# Reference_distribution.net
KiCad netlist of a schematic drawn in Altium Designer
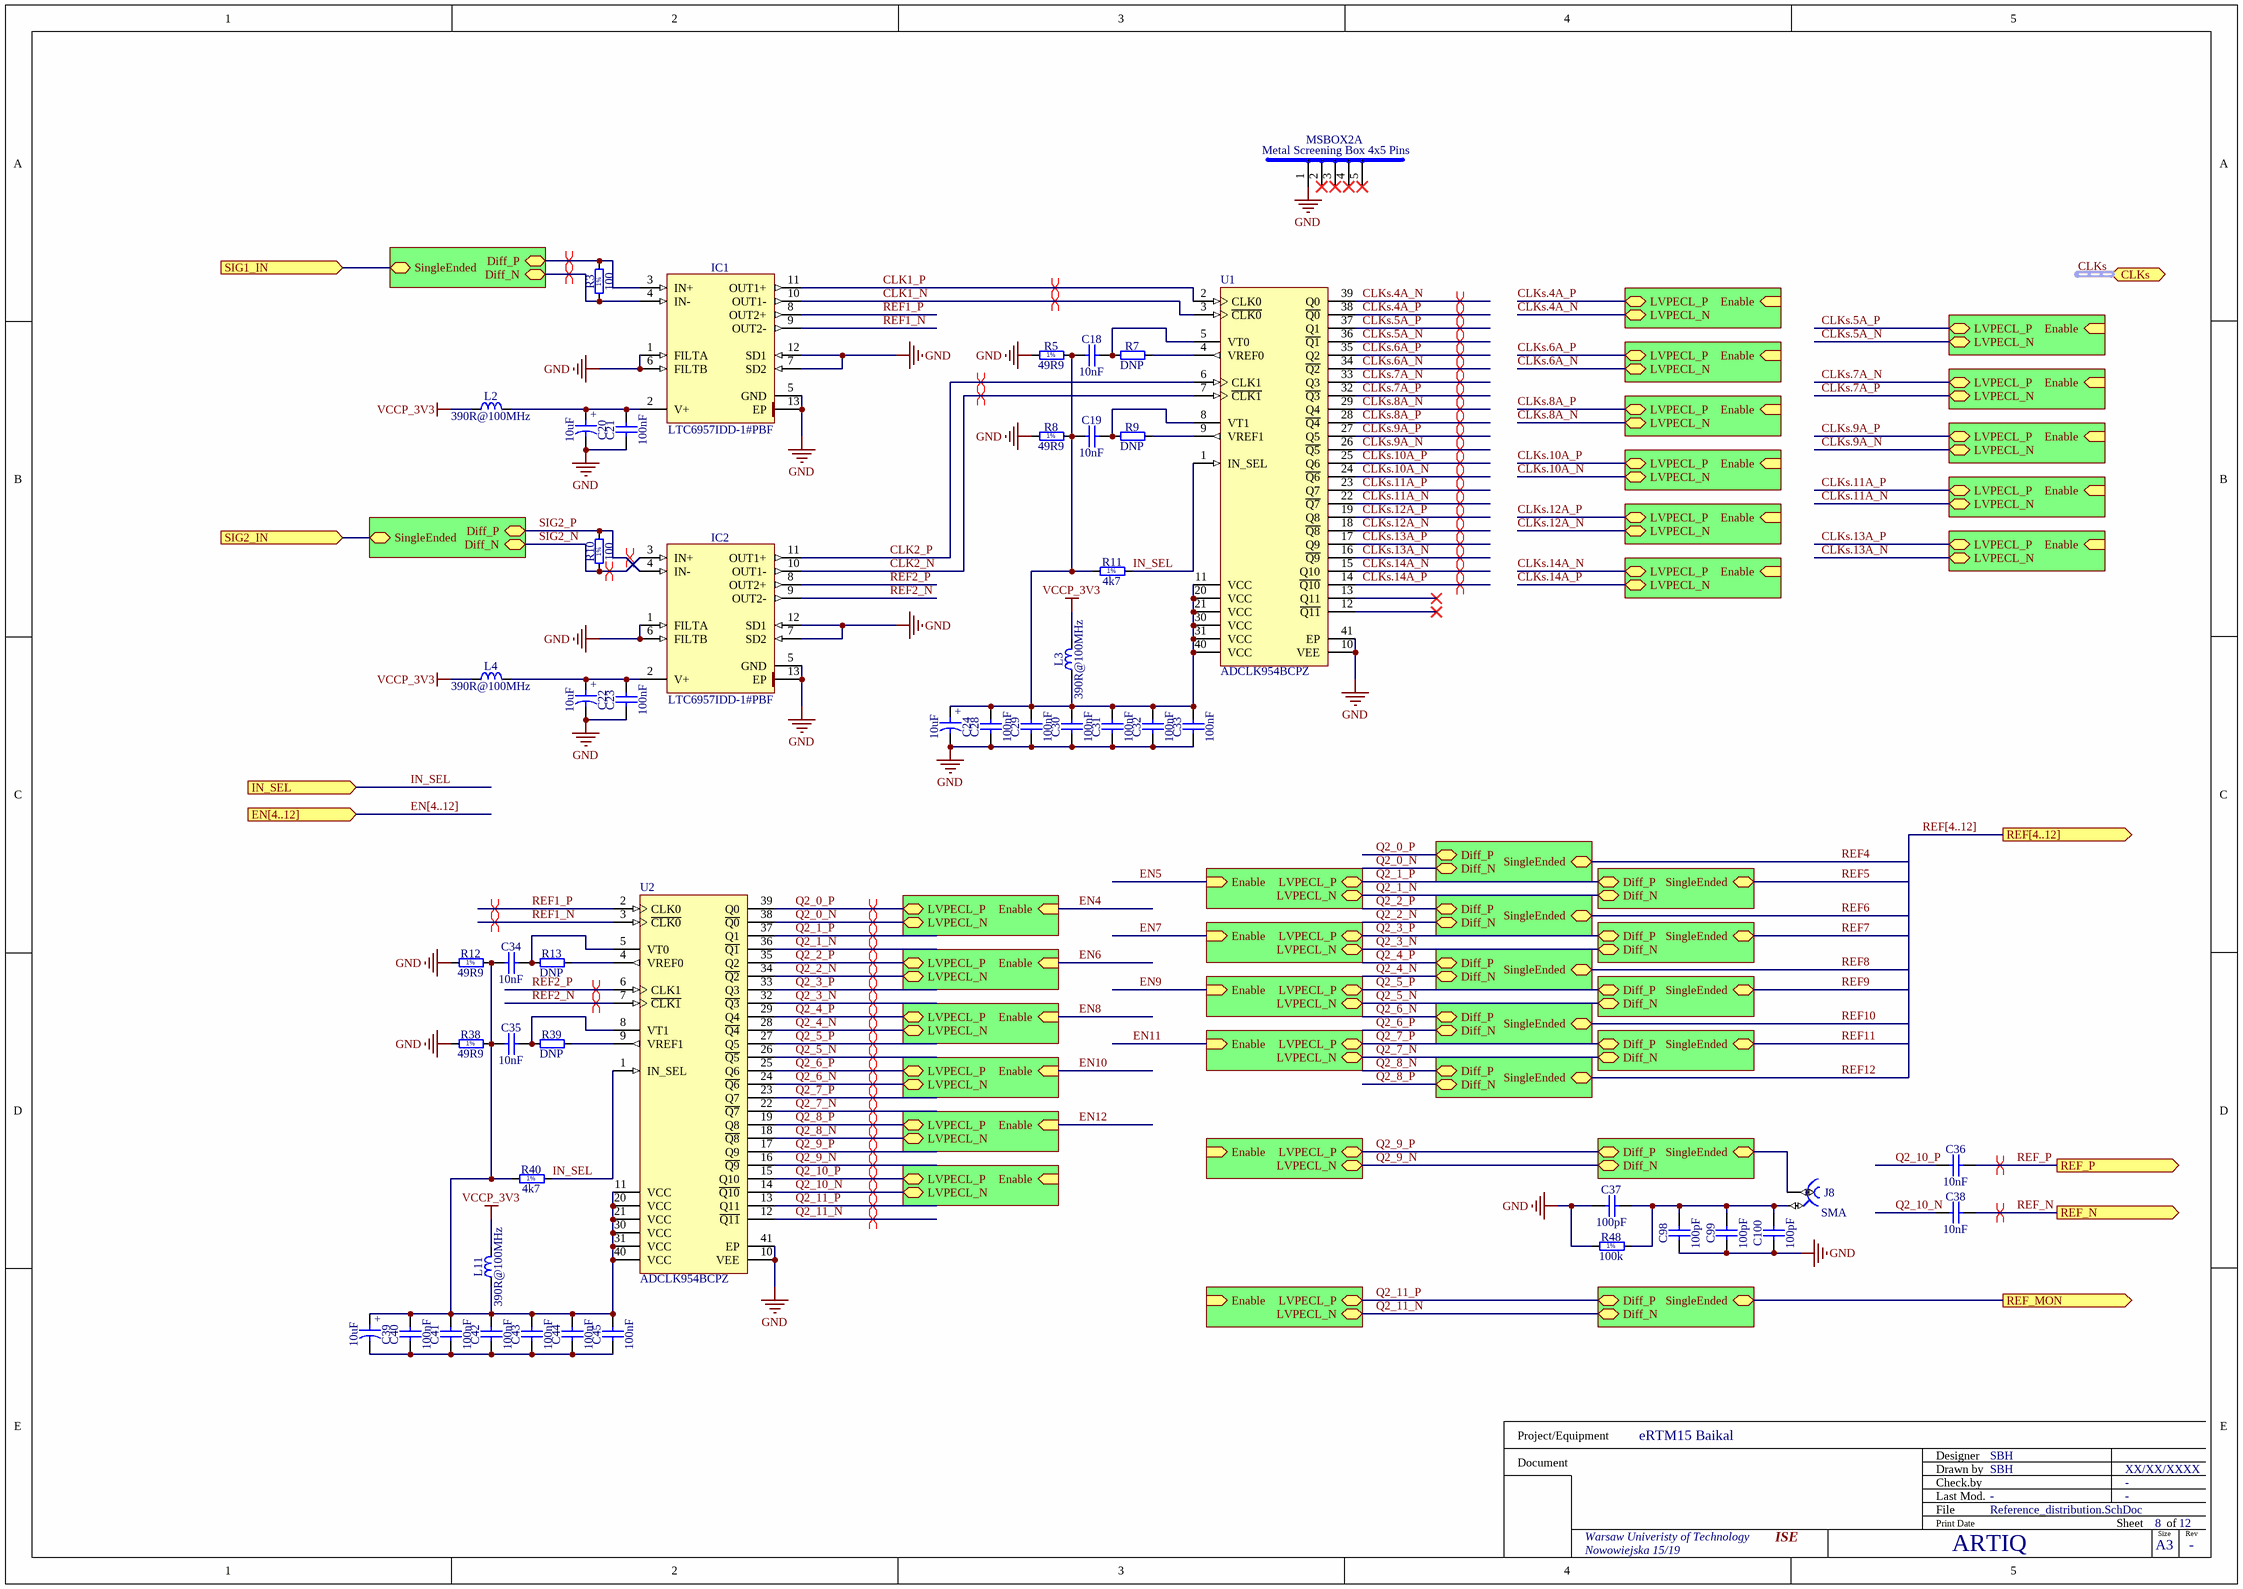
[diagram p0: Reference_distribution.SchDoc]

(export (version "E")
  (design (tool "Eeschema 10.0.6"))
  (components
    (comp (ref "C18")
      (value "10nF")
      (footprint "CAPC1005X55N")
      (description "Non-polarised capacitor")
      (fields
        (field (name "PART NUMBER") "CC0402_10NF_16V_10%_X7R")
        (field (name "VOLTAGE") "16V")
        (field (name "AUTHOR") "CERN DEM JLC")
      )
      (libsource (lib "Capacitors") (part "Capacitor - non polarized"))
    )
    (comp (ref "C19")
      (value "10nF")
      (footprint "CAPC1005X55N")
      (description "Non-polarised capacitor")
      (fields
        (field (name "PART NUMBER") "CC0402_10NF_16V_10%_X7R")
        (field (name "VOLTAGE") "16V")
        (field (name "AUTHOR") "CERN DEM JLC")
      )
      (libsource (lib "Capacitors") (part "Capacitor - non polarized"))
    )
    (comp (ref "C20")
      (value "10uF")
      (footprint "CAPMP3216X180N")
      (description "Polarised capacitor")
      (fields
        (field (name "PART NUMBER") "CTE3216-18_10UF_10V_10%_LESR1800")
        (field (name "VOLTAGE") "10V")
        (field (name "AUTHOR") "CERN DEM JLC")
      )
      (libsource (lib "Capacitors") (part "Capacitor - polarized"))
    )
    (comp (ref "C21")
      (value "100nF")
      (footprint "CAPC1005X55N")
      (description "Non-polarised capacitor")
      (fields
        (field (name "PART NUMBER") "CC0402_100NF_16V_10%_X7R")
        (field (name "VOLTAGE") "16V")
        (field (name "AUTHOR") "CERN DEM JLC")
      )
      (libsource (lib "Capacitors") (part "Capacitor - non polarized"))
    )
    (comp (ref "C22")
      (value "10uF")
      (footprint "CAPMP3216X180N")
      (description "Polarised capacitor")
      (fields
        (field (name "PART NUMBER") "CTE3216-18_10UF_10V_10%_LESR1800")
        (field (name "VOLTAGE") "10V")
        (field (name "AUTHOR") "CERN DEM JLC")
      )
      (libsource (lib "Capacitors") (part "Capacitor - polarized"))
    )
    (comp (ref "C23")
      (value "100nF")
      (footprint "CAPC1005X55N")
      (description "Non-polarised capacitor")
      (fields
        (field (name "PART NUMBER") "CC0402_100NF_16V_10%_X7R")
        (field (name "VOLTAGE") "16V")
        (field (name "AUTHOR") "CERN DEM JLC")
      )
      (libsource (lib "Capacitors") (part "Capacitor - non polarized"))
    )
    (comp (ref "C24")
      (value "10uF")
      (footprint "CAPMP3216X180N")
      (description "Polarised capacitor")
      (fields
        (field (name "PART NUMBER") "CTE3216-18_10UF_10V_10%_LESR1800")
        (field (name "VOLTAGE") "10V")
        (field (name "AUTHOR") "CERN DEM JLC")
      )
      (libsource (lib "Capacitors") (part "Capacitor - polarized"))
    )
    (comp (ref "C28")
      (value "100nF")
      (footprint "CAPC1005X55N")
      (description "Non-polarised capacitor")
      (fields
        (field (name "PART NUMBER") "CC0402_100NF_16V_10%_X7R")
        (field (name "VOLTAGE") "16V")
        (field (name "AUTHOR") "CERN DEM JLC")
      )
      (libsource (lib "Capacitors") (part "Capacitor - non polarized"))
    )
    (comp (ref "C29")
      (value "100nF")
      (footprint "CAPC1005X55N")
      (description "Non-polarised capacitor")
      (fields
        (field (name "PART NUMBER") "CC0402_100NF_16V_10%_X7R")
        (field (name "VOLTAGE") "16V")
        (field (name "AUTHOR") "CERN DEM JLC")
      )
      (libsource (lib "Capacitors") (part "Capacitor - non polarized"))
    )
    (comp (ref "C30")
      (value "100nF")
      (footprint "CAPC1005X55N")
      (description "Non-polarised capacitor")
      (fields
        (field (name "PART NUMBER") "CC0402_100NF_16V_10%_X7R")
        (field (name "VOLTAGE") "16V")
        (field (name "AUTHOR") "CERN DEM JLC")
      )
      (libsource (lib "Capacitors") (part "Capacitor - non polarized"))
    )
    (comp (ref "C31")
      (value "100nF")
      (footprint "CAPC1005X55N")
      (description "Non-polarised capacitor")
      (fields
        (field (name "PART NUMBER") "CC0402_100NF_16V_10%_X7R")
        (field (name "VOLTAGE") "16V")
        (field (name "AUTHOR") "CERN DEM JLC")
      )
      (libsource (lib "Capacitors") (part "Capacitor - non polarized"))
    )
    (comp (ref "C32")
      (value "100nF")
      (footprint "CAPC1005X55N")
      (description "Non-polarised capacitor")
      (fields
        (field (name "PART NUMBER") "CC0402_100NF_16V_10%_X7R")
        (field (name "VOLTAGE") "16V")
        (field (name "AUTHOR") "CERN DEM JLC")
      )
      (libsource (lib "Capacitors") (part "Capacitor - non polarized"))
    )
    (comp (ref "C33")
      (value "100nF")
      (footprint "CAPC1005X55N")
      (description "Non-polarised capacitor")
      (fields
        (field (name "PART NUMBER") "CC0402_100NF_16V_10%_X7R")
        (field (name "VOLTAGE") "16V")
        (field (name "AUTHOR") "CERN DEM JLC")
      )
      (libsource (lib "Capacitors") (part "Capacitor - non polarized"))
    )
    (comp (ref "C34")
      (value "10nF")
      (footprint "CAPC1005X55N")
      (description "Non-polarised capacitor")
      (fields
        (field (name "PART NUMBER") "CC0402_10NF_16V_10%_X7R")
        (field (name "VOLTAGE") "16V")
        (field (name "AUTHOR") "CERN DEM JLC")
      )
      (libsource (lib "Capacitors") (part "Capacitor - non polarized"))
    )
    (comp (ref "C35")
      (value "10nF")
      (footprint "CAPC1005X55N")
      (description "Non-polarised capacitor")
      (fields
        (field (name "PART NUMBER") "CC0402_10NF_16V_10%_X7R")
        (field (name "VOLTAGE") "16V")
        (field (name "AUTHOR") "CERN DEM JLC")
      )
      (libsource (lib "Capacitors") (part "Capacitor - non polarized"))
    )
    (comp (ref "C36")
      (value "10nF")
      (footprint "CAPC1005X55N")
      (description "Non-polarised capacitor")
      (fields
        (field (name "PART NUMBER") "CC0402_10NF_16V_10%_X7R")
        (field (name "VOLTAGE") "16V")
        (field (name "AUTHOR") "CERN DEM JLC")
      )
      (libsource (lib "Capacitors") (part "Capacitor - non polarized"))
    )
    (comp (ref "C37")
      (value "100pF")
      (footprint "CAPC1005X55N")
      (description "Non-polarised capacitor")
      (fields
        (field (name "PART NUMBER") "CC0402_100PF_50V_5%_C0G")
        (field (name "VOLTAGE") "50V")
        (field (name "AUTHOR") "CERN DEM JLC")
      )
      (libsource (lib "Capacitors") (part "Capacitor - non polarized"))
    )
    (comp (ref "C38")
      (value "10nF")
      (footprint "CAPC1005X55N")
      (description "Non-polarised capacitor")
      (fields
        (field (name "PART NUMBER") "CC0402_10NF_16V_10%_X7R")
        (field (name "VOLTAGE") "16V")
        (field (name "AUTHOR") "CERN DEM JLC")
      )
      (libsource (lib "Capacitors") (part "Capacitor - non polarized"))
    )
    (comp (ref "C39")
      (value "10uF")
      (footprint "CAPMP3216X180N")
      (description "Polarised capacitor")
      (fields
        (field (name "PART NUMBER") "CTE3216-18_10UF_10V_10%_LESR1800")
        (field (name "VOLTAGE") "10V")
        (field (name "AUTHOR") "CERN DEM JLC")
      )
      (libsource (lib "Capacitors") (part "Capacitor - polarized"))
    )
    (comp (ref "C40")
      (value "100nF")
      (footprint "CAPC1005X55N")
      (description "Non-polarised capacitor")
      (fields
        (field (name "PART NUMBER") "CC0402_100NF_16V_10%_X7R")
        (field (name "VOLTAGE") "16V")
        (field (name "AUTHOR") "CERN DEM JLC")
      )
      (libsource (lib "Capacitors") (part "Capacitor - non polarized"))
    )
    (comp (ref "C41")
      (value "100nF")
      (footprint "CAPC1005X55N")
      (description "Non-polarised capacitor")
      (fields
        (field (name "PART NUMBER") "CC0402_100NF_16V_10%_X7R")
        (field (name "VOLTAGE") "16V")
        (field (name "AUTHOR") "CERN DEM JLC")
      )
      (libsource (lib "Capacitors") (part "Capacitor - non polarized"))
    )
    (comp (ref "C42")
      (value "100nF")
      (footprint "CAPC1005X55N")
      (description "Non-polarised capacitor")
      (fields
        (field (name "PART NUMBER") "CC0402_100NF_16V_10%_X7R")
        (field (name "VOLTAGE") "16V")
        (field (name "AUTHOR") "CERN DEM JLC")
      )
      (libsource (lib "Capacitors") (part "Capacitor - non polarized"))
    )
    (comp (ref "C43")
      (value "100nF")
      (footprint "CAPC1005X55N")
      (description "Non-polarised capacitor")
      (fields
        (field (name "PART NUMBER") "CC0402_100NF_16V_10%_X7R")
        (field (name "VOLTAGE") "16V")
        (field (name "AUTHOR") "CERN DEM JLC")
      )
      (libsource (lib "Capacitors") (part "Capacitor - non polarized"))
    )
    (comp (ref "C44")
      (value "100nF")
      (footprint "CAPC1005X55N")
      (description "Non-polarised capacitor")
      (fields
        (field (name "PART NUMBER") "CC0402_100NF_16V_10%_X7R")
        (field (name "VOLTAGE") "16V")
        (field (name "AUTHOR") "CERN DEM JLC")
      )
      (libsource (lib "Capacitors") (part "Capacitor - non polarized"))
    )
    (comp (ref "C45")
      (value "100nF")
      (footprint "CAPC1005X55N")
      (description "Non-polarised capacitor")
      (fields
        (field (name "PART NUMBER") "CC0402_100NF_16V_10%_X7R")
        (field (name "VOLTAGE") "16V")
        (field (name "AUTHOR") "CERN DEM JLC")
      )
      (libsource (lib "Capacitors") (part "Capacitor - non polarized"))
    )
    (comp (ref "C98")
      (value "100pF")
      (footprint "CAPC1005X55N")
      (description "Non-polarised capacitor")
      (fields
        (field (name "PART NUMBER") "CC0402_100PF_50V_5%_C0G")
        (field (name "VOLTAGE") "50V")
        (field (name "AUTHOR") "CERN DEM JLC")
      )
      (libsource (lib "Capacitors") (part "Capacitor - non polarized"))
    )
    (comp (ref "C99")
      (value "100pF")
      (footprint "CAPC1005X55N")
      (description "Non-polarised capacitor")
      (fields
        (field (name "PART NUMBER") "CC0402_100PF_50V_5%_C0G")
        (field (name "VOLTAGE") "50V")
        (field (name "AUTHOR") "CERN DEM JLC")
      )
      (libsource (lib "Capacitors") (part "Capacitor - non polarized"))
    )
    (comp (ref "C100")
      (value "100pF")
      (footprint "CAPC1005X55N")
      (description "Non-polarised capacitor")
      (fields
        (field (name "PART NUMBER") "CC0402_100PF_50V_5%_C0G")
        (field (name "VOLTAGE") "50V")
        (field (name "AUTHOR") "CERN DEM JLC")
      )
      (libsource (lib "Capacitors") (part "Capacitor - non polarized"))
    )
    (comp (ref "IC1")
      (value "LTC6957IDD-1#PBF")
      (footprint "SON45P300X300X80-13N-R175X248")
      (description "Low Phase Noise, Dual Output Buffer/Driver/Logic Converter, LVPECL Logic Outputs")
      (fields (field (name "MANUFACTURER") "LINEAR TECHNOLOGY") (field (name "AUTHOR") "CERN DEM JLC"))
      (libsource (lib "ICs And Semiconductors") (part "LTC6957IDD-1"))
    )
    (comp (ref "IC2")
      (value "LTC6957IDD-1#PBF")
      (footprint "SON45P300X300X80-13N-R175X248")
      (description "Low Phase Noise, Dual Output Buffer/Driver/Logic Converter, LVPECL Logic Outputs")
      (fields (field (name "MANUFACTURER") "LINEAR TECHNOLOGY") (field (name "AUTHOR") "CERN DEM JLC"))
      (libsource (lib "ICs And Semiconductors") (part "LTC6957IDD-1"))
    )
    (comp (ref "J8")
      (value "SMA")
      (footprint "HUBER-SUHNER_82_SMA-50-0-41/133_NE")
      (fields
        (field (name "PART NUMBER") "HUBER-SUHNER_82_SMA-50-0-41/133_NE")
        (field (name "MANUFACTURER") "HUBER+SUHNER")
        (field (name "MANUFACTURER PART NUMBER") "82_SMA-50-0-41/133_NE")
        (field (name "AUTHOR") "CERN DEM JLC")
      )
      (libsource (lib "Connectors") (part "Coax_1Female_1Shield"))
    )
    (comp (ref "L2")
      (value "390R@100MHz")
      (footprint "INDC1608X95N")
      (description "Inductor")
      (fields
        (field (name "PART NUMBER") "IND0603_TDK_MPZ1608R391A")
        (field (name "POWER") "1.2A")
        (field (name "AUTHOR") "CERN DEM JLC")
      )
      (libsource (lib "Inductors & Transformers") (part "Inductor"))
    )
    (comp (ref "L3")
      (value "390R@100MHz")
      (footprint "INDC1608X95N")
      (description "Inductor")
      (fields
        (field (name "PART NUMBER") "IND0603_TDK_MPZ1608R391A")
        (field (name "POWER") "1.2A")
        (field (name "AUTHOR") "CERN DEM JLC")
      )
      (libsource (lib "") (part "Inductor_1"))
    )
    (comp (ref "L4")
      (value "390R@100MHz")
      (footprint "INDC1608X95N")
      (description "Inductor")
      (fields
        (field (name "PART NUMBER") "IND0603_TDK_MPZ1608R391A")
        (field (name "POWER") "1.2A")
        (field (name "AUTHOR") "CERN DEM JLC")
      )
      (libsource (lib "Inductors & Transformers") (part "Inductor"))
    )
    (comp (ref "L11")
      (value "390R@100MHz")
      (footprint "INDC1608X95N")
      (description "Inductor")
      (fields
        (field (name "PART NUMBER") "IND0603_TDK_MPZ1608R391A")
        (field (name "POWER") "1.2A")
        (field (name "AUTHOR") "CERN DEM JLC")
      )
      (libsource (lib "") (part "Inductor_1"))
    )
    (comp (ref "MSBOX2")
      (value "Metal Screening Box 4x5 Pins")
      (footprint "MSBOX_WURTH_36103305")
      (description "Metal Screening Box 20 (4x5) Pins")
      (fields
        (field (name "PART NUMBER") "MSBOX_WURTH_36103305")
        (field (name "MANUFACTURER") "WURTH")
        (field (name "AUTHOR") "CERN DEM JLC")
      )
      (libsource (lib "Eletro-mechanical") (part "Metal Screening Box - 4x5 pins"))
    )
    (comp (ref "R3")
      (value "100")
      (footprint "RESC1005X40N")
      (description "Resistor - 1%")
      (fields
        (field (name "PART NUMBER") "R0402_100R_1%_0.0625W_100PPM")
        (field (name "POWER") "0.0625W")
        (field (name "AUTHOR") "CERN DEM JLC")
      )
      (libsource (lib "Resistors") (part "Resistor - 1%"))
    )
    (comp (ref "R5")
      (value "49R9")
      (footprint "RESC1005X40N")
      (description "Resistor - 1%")
      (fields
        (field (name "PART NUMBER") "R0402_49R9_1%_0.0625W_100PPM")
        (field (name "POWER") "0.0625W")
        (field (name "AUTHOR") "CERN DEM JLC")
      )
      (libsource (lib "Resistors") (part "Resistor - 1%"))
    )
    (comp (ref "R7")
      (value "DNP")
      (footprint "RESC1005X40N")
      (description "Resistor")
      (fields
        (field (name "PART NUMBER") "R0402_0R_JUMPER")
        (field (name "MANUFACTURER") "GENERIC")
        (field (name "AUTHOR") "CERN DEM JLC")
      )
      (libsource (lib "Resistors") (part "Resistor"))
    )
    (comp (ref "R8")
      (value "49R9")
      (footprint "RESC1005X40N")
      (description "Resistor - 1%")
      (fields
        (field (name "PART NUMBER") "R0402_49R9_1%_0.0625W_100PPM")
        (field (name "POWER") "0.0625W")
        (field (name "AUTHOR") "CERN DEM JLC")
      )
      (libsource (lib "Resistors") (part "Resistor - 1%"))
    )
    (comp (ref "R9")
      (value "DNP")
      (footprint "RESC1005X40N")
      (description "Resistor")
      (fields
        (field (name "PART NUMBER") "R0402_0R_JUMPER")
        (field (name "MANUFACTURER") "GENERIC")
        (field (name "AUTHOR") "CERN DEM JLC")
      )
      (libsource (lib "Resistors") (part "Resistor"))
    )
    (comp (ref "R10")
      (value "100")
      (footprint "RESC1005X40N")
      (description "Resistor - 1%")
      (fields
        (field (name "PART NUMBER") "R0402_100R_1%_0.0625W_100PPM")
        (field (name "POWER") "0.0625W")
        (field (name "AUTHOR") "CERN DEM JLC")
      )
      (libsource (lib "Resistors") (part "Resistor - 1%"))
    )
    (comp (ref "R11")
      (value "4k7")
      (footprint "RESC1005X40N")
      (description "Resistor - 1%")
      (fields
        (field (name "PART NUMBER") "R0402_4K7_1%_0.0625W_100PPM")
        (field (name "POWER") "0.0625W")
        (field (name "AUTHOR") "CERN DEM JLC")
      )
      (libsource (lib "Resistors") (part "Resistor - 1%"))
    )
    (comp (ref "R12")
      (value "49R9")
      (footprint "RESC1005X40N")
      (description "Resistor - 1%")
      (fields
        (field (name "PART NUMBER") "R0402_49R9_1%_0.0625W_100PPM")
        (field (name "POWER") "0.0625W")
        (field (name "AUTHOR") "CERN DEM JLC")
      )
      (libsource (lib "Resistors") (part "Resistor - 1%"))
    )
    (comp (ref "R13")
      (value "DNP")
      (footprint "RESC1005X40N")
      (description "Resistor")
      (fields
        (field (name "PART NUMBER") "R0402_0R_JUMPER")
        (field (name "MANUFACTURER") "GENERIC")
        (field (name "AUTHOR") "CERN DEM JLC")
      )
      (libsource (lib "Resistors") (part "Resistor"))
    )
    (comp (ref "R38")
      (value "49R9")
      (footprint "RESC1005X40N")
      (description "Resistor - 1%")
      (fields
        (field (name "PART NUMBER") "R0402_49R9_1%_0.0625W_100PPM")
        (field (name "POWER") "0.0625W")
        (field (name "AUTHOR") "CERN DEM JLC")
      )
      (libsource (lib "Resistors") (part "Resistor - 1%"))
    )
    (comp (ref "R39")
      (value "DNP")
      (footprint "RESC1005X40N")
      (description "Resistor")
      (fields
        (field (name "PART NUMBER") "R0402_0R_JUMPER")
        (field (name "MANUFACTURER") "GENERIC")
        (field (name "AUTHOR") "CERN DEM JLC")
      )
      (libsource (lib "Resistors") (part "Resistor"))
    )
    (comp (ref "R40")
      (value "4k7")
      (footprint "RESC1005X40N")
      (description "Resistor - 1%")
      (fields
        (field (name "PART NUMBER") "R0402_4K7_1%_0.0625W_100PPM")
        (field (name "POWER") "0.0625W")
        (field (name "AUTHOR") "CERN DEM JLC")
      )
      (libsource (lib "Resistors") (part "Resistor - 1%"))
    )
    (comp (ref "R48")
      (value "100k")
      (footprint "RESC1005X40N")
      (description "Resistor - 1%")
      (fields
        (field (name "PART NUMBER") "R0402_100k_1%_0.0625W_100PPM")
        (field (name "POWER") "0.0625W")
        (field (name "AUTHOR") "CERN DEM JLC")
      )
      (libsource (lib "Resistors") (part "Resistor - 1%"))
    )
    (comp (ref "U1")
      (value "ADCLK954BCPZ")
      (footprint "ADI-CP-40-8_M")
      (fields (field (name "MANUFACTURER") "Analog Devices"))
      (libsource (lib "Altium Content Vault") (part "ADI-ADCLK954-CP-40-8"))
    )
    (comp (ref "U2")
      (value "ADCLK954BCPZ")
      (footprint "ADI-CP-40-8_M")
      (fields (field (name "MANUFACTURER") "Analog Devices"))
      (libsource (lib "Altium Content Vault") (part "ADI-ADCLK954-CP-40-8"))
    )
  )
  (nets
    (net (code "2") (name "/CLK1_N") (class "Default")
      (node (ref "IC1") (pin "10") (pinfunction "OUT1-_10") (pintype "output"))
      (node (ref "U1") (pin "3") (pinfunction "~{CLK0}_3") (pintype "input"))
    )
    (net (code "3") (name "/CLK1_P") (class "Default")
      (node (ref "IC1") (pin "11") (pinfunction "OUT1+_11") (pintype "output"))
      (node (ref "U1") (pin "2") (pinfunction "CLK0_2") (pintype "input"))
    )
    (net (code "4") (name "/CLK2_N") (class "Default")
      (node (ref "IC2") (pin "10") (pinfunction "OUT1-_10") (pintype "output"))
      (node (ref "U1") (pin "7") (pinfunction "~{CLK1}_7") (pintype "input"))
    )
    (net (code "5") (name "/CLK2_P") (class "Default")
      (node (ref "IC2") (pin "11") (pinfunction "OUT1+_11") (pintype "output"))
      (node (ref "U1") (pin "6") (pinfunction "CLK1_6") (pintype "input"))
    )
    (net (code "6") (name "/CLKs.4A_N") (class "Default")
      (node (ref "U1") (pin "39") (pinfunction "Q0_39") (pintype "open_emitter"))
    )
    (net (code "7") (name "/CLKs.4A_P") (class "Default")
      (node (ref "U1") (pin "38") (pinfunction "~{Q0}_38") (pintype "open_emitter"))
    )
    (net (code "8") (name "/CLKs.5A_N") (class "Default")
      (node (ref "U1") (pin "36") (pinfunction "~{Q1}_36") (pintype "open_emitter"))
    )
    (net (code "9") (name "/CLKs.5A_P") (class "Default")
      (node (ref "U1") (pin "37") (pinfunction "Q1_37") (pintype "open_emitter"))
    )
    (net (code "10") (name "/CLKs.6A_N") (class "Default")
      (node (ref "U1") (pin "34") (pinfunction "~{Q2}_34") (pintype "open_emitter"))
    )
    (net (code "11") (name "/CLKs.6A_P") (class "Default")
      (node (ref "U1") (pin "35") (pinfunction "Q2_35") (pintype "open_emitter"))
    )
    (net (code "12") (name "/CLKs.7A_N") (class "Default")
      (node (ref "U1") (pin "33") (pinfunction "Q3_33") (pintype "open_emitter"))
    )
    (net (code "13") (name "/CLKs.7A_P") (class "Default")
      (node (ref "U1") (pin "32") (pinfunction "~{Q3}_32") (pintype "open_emitter"))
    )
    (net (code "14") (name "/CLKs.8A_N") (class "Default")
      (node (ref "U1") (pin "29") (pinfunction "Q4_29") (pintype "open_emitter"))
    )
    (net (code "15") (name "/CLKs.8A_P") (class "Default")
      (node (ref "U1") (pin "28") (pinfunction "~{Q4}_28") (pintype "open_emitter"))
    )
    (net (code "16") (name "/CLKs.9A_N") (class "Default")
      (node (ref "U1") (pin "26") (pinfunction "~{Q5}_26") (pintype "open_emitter"))
    )
    (net (code "17") (name "/CLKs.9A_P") (class "Default")
      (node (ref "U1") (pin "27") (pinfunction "Q5_27") (pintype "open_emitter"))
    )
    (net (code "18") (name "/CLKs.10A_N") (class "Default")
      (node (ref "U1") (pin "24") (pinfunction "~{Q6}_24") (pintype "open_emitter"))
    )
    (net (code "19") (name "/CLKs.10A_P") (class "Default")
      (node (ref "U1") (pin "25") (pinfunction "Q6_25") (pintype "open_emitter"))
    )
    (net (code "20") (name "/CLKs.11A_N") (class "Default")
      (node (ref "U1") (pin "22") (pinfunction "~{Q7}_22") (pintype "open_emitter"))
    )
    (net (code "21") (name "/CLKs.11A_P") (class "Default")
      (node (ref "U1") (pin "23") (pinfunction "Q7_23") (pintype "open_emitter"))
    )
    (net (code "22") (name "/CLKs.12A_N") (class "Default")
      (node (ref "U1") (pin "18") (pinfunction "~{Q8}_18") (pintype "open_emitter"))
    )
    (net (code "23") (name "/CLKs.12A_P") (class "Default")
      (node (ref "U1") (pin "19") (pinfunction "Q8_19") (pintype "open_emitter"))
    )
    (net (code "24") (name "/CLKs.13A_N") (class "Default")
      (node (ref "U1") (pin "16") (pinfunction "~{Q9}_16") (pintype "open_emitter"))
    )
    (net (code "25") (name "/CLKs.13A_P") (class "Default")
      (node (ref "U1") (pin "17") (pinfunction "Q9_17") (pintype "open_emitter"))
    )
    (net (code "26") (name "/CLKs.14A_N") (class "Default")
      (node (ref "U1") (pin "15") (pinfunction "Q10_15") (pintype "open_emitter"))
    )
    (net (code "27") (name "/CLKs.14A_P") (class "Default")
      (node (ref "U1") (pin "14") (pinfunction "~{Q10}_14") (pintype "open_emitter"))
    )
    (net (code "28") (name "/Diff_N") (class "Default")
      (node (ref "IC1") (pin "4") (pinfunction "IN-_4") (pintype "input"))
      (node (ref "R3") (pin "1") (pinfunction "1_1") (pintype "passive"))
    )
    (net (code "29") (name "/Diff_P") (class "Default")
      (node (ref "IC1") (pin "3") (pinfunction "IN+_3") (pintype "input"))
      (node (ref "R3") (pin "2") (pinfunction "2_2") (pintype "passive"))
    )
    (net (code "54") (name "/IN_SEL") (class "Default")
      (node (ref "R11") (pin "2") (pinfunction "2_2") (pintype "passive"))
      (node (ref "R40") (pin "2") (pinfunction "2_2") (pintype "passive"))
      (node (ref "U1") (pin "1") (pinfunction "IN_SEL_1") (pintype "input"))
      (node (ref "U2") (pin "1") (pinfunction "IN_SEL_1") (pintype "input"))
    )
    (net (code "55") (name "/Q2_0_N") (class "Default")
      (node (ref "U2") (pin "38") (pinfunction "~{Q0}_38") (pintype "open_emitter"))
    )
    (net (code "56") (name "/Q2_0_P") (class "Default")
      (node (ref "U2") (pin "39") (pinfunction "Q0_39") (pintype "open_emitter"))
    )
    (net (code "57") (name "/Q2_1_N") (class "Default")
      (node (ref "U2") (pin "36") (pinfunction "~{Q1}_36") (pintype "open_emitter"))
    )
    (net (code "58") (name "/Q2_1_P") (class "Default")
      (node (ref "U2") (pin "37") (pinfunction "Q1_37") (pintype "open_emitter"))
    )
    (net (code "59") (name "/Q2_2_N") (class "Default")
      (node (ref "U2") (pin "34") (pinfunction "~{Q2}_34") (pintype "open_emitter"))
    )
    (net (code "60") (name "/Q2_2_P") (class "Default")
      (node (ref "U2") (pin "35") (pinfunction "Q2_35") (pintype "open_emitter"))
    )
    (net (code "61") (name "/Q2_3_N") (class "Default")
      (node (ref "U2") (pin "32") (pinfunction "~{Q3}_32") (pintype "open_emitter"))
    )
    (net (code "62") (name "/Q2_3_P") (class "Default")
      (node (ref "U2") (pin "33") (pinfunction "Q3_33") (pintype "open_emitter"))
    )
    (net (code "63") (name "/Q2_4_N") (class "Default")
      (node (ref "U2") (pin "28") (pinfunction "~{Q4}_28") (pintype "open_emitter"))
    )
    (net (code "64") (name "/Q2_4_P") (class "Default")
      (node (ref "U2") (pin "29") (pinfunction "Q4_29") (pintype "open_emitter"))
    )
    (net (code "65") (name "/Q2_5_N") (class "Default")
      (node (ref "U2") (pin "26") (pinfunction "~{Q5}_26") (pintype "open_emitter"))
    )
    (net (code "66") (name "/Q2_5_P") (class "Default")
      (node (ref "U2") (pin "27") (pinfunction "Q5_27") (pintype "open_emitter"))
    )
    (net (code "67") (name "/Q2_6_N") (class "Default")
      (node (ref "U2") (pin "24") (pinfunction "~{Q6}_24") (pintype "open_emitter"))
    )
    (net (code "68") (name "/Q2_6_P") (class "Default")
      (node (ref "U2") (pin "25") (pinfunction "Q6_25") (pintype "open_emitter"))
    )
    (net (code "69") (name "/Q2_7_N") (class "Default")
      (node (ref "U2") (pin "22") (pinfunction "~{Q7}_22") (pintype "open_emitter"))
    )
    (net (code "70") (name "/Q2_7_P") (class "Default")
      (node (ref "U2") (pin "23") (pinfunction "Q7_23") (pintype "open_emitter"))
    )
    (net (code "71") (name "/Q2_8_N") (class "Default")
      (node (ref "U2") (pin "18") (pinfunction "~{Q8}_18") (pintype "open_emitter"))
    )
    (net (code "72") (name "/Q2_8_P") (class "Default")
      (node (ref "U2") (pin "19") (pinfunction "Q8_19") (pintype "open_emitter"))
    )
    (net (code "73") (name "/Q2_9_N") (class "Default")
      (node (ref "U2") (pin "16") (pinfunction "~{Q9}_16") (pintype "open_emitter"))
    )
    (net (code "74") (name "/Q2_9_P") (class "Default")
      (node (ref "U2") (pin "17") (pinfunction "Q9_17") (pintype "open_emitter"))
    )
    (net (code "75") (name "/Q2_10_N") (class "Default")
      (node (ref "C38") (pin "1") (pinfunction "1_1") (pintype "passive"))
      (node (ref "U2") (pin "14") (pinfunction "~{Q10}_14") (pintype "open_emitter"))
    )
    (net (code "76") (name "/Q2_10_P") (class "Default")
      (node (ref "C36") (pin "1") (pinfunction "1_1") (pintype "passive"))
      (node (ref "U2") (pin "15") (pinfunction "Q10_15") (pintype "open_emitter"))
    )
    (net (code "77") (name "/Q2_11_N") (class "Default")
      (node (ref "U2") (pin "12") (pinfunction "~{Q11}_12") (pintype "open_emitter"))
    )
    (net (code "78") (name "/Q2_11_P") (class "Default")
      (node (ref "U2") (pin "13") (pinfunction "Q11_13") (pintype "open_emitter"))
    )
    (net (code "79") (name "/REF1_N") (class "Default")
      (node (ref "IC1") (pin "9") (pinfunction "OUT2-_9") (pintype "output"))
      (node (ref "U2") (pin "3") (pinfunction "~{CLK0}_3") (pintype "input"))
    )
    (net (code "80") (name "/REF1_P") (class "Default")
      (node (ref "IC1") (pin "8") (pinfunction "OUT2+_8") (pintype "output"))
      (node (ref "U2") (pin "2") (pinfunction "CLK0_2") (pintype "input"))
    )
    (net (code "81") (name "/REF2_N") (class "Default")
      (node (ref "IC2") (pin "9") (pinfunction "OUT2-_9") (pintype "output"))
      (node (ref "U2") (pin "7") (pinfunction "~{CLK1}_7") (pintype "input"))
    )
    (net (code "82") (name "/REF2_P") (class "Default")
      (node (ref "IC2") (pin "8") (pinfunction "OUT2+_8") (pintype "output"))
      (node (ref "U2") (pin "6") (pinfunction "CLK1_6") (pintype "input"))
    )
    (net (code "94") (name "/REF_N") (class "Default")
      (node (ref "C38") (pin "2") (pinfunction "2_2") (pintype "passive"))
    )
    (net (code "95") (name "/REF_P") (class "Default")
      (node (ref "C36") (pin "2") (pinfunction "2_2") (pintype "passive"))
    )
    (net (code "98") (name "/SIG2_N") (class "Default")
      (node (ref "IC2") (pin "3") (pinfunction "IN+_3") (pintype "input"))
      (node (ref "R10") (pin "1") (pinfunction "1_1") (pintype "passive"))
    )
    (net (code "99") (name "/SIG2_P") (class "Default")
      (node (ref "IC2") (pin "4") (pinfunction "IN-_4") (pintype "input"))
      (node (ref "R10") (pin "2") (pinfunction "2_2") (pintype "passive"))
    )
    (net (code "100") (name "/SingleEnded") (class "Default")
      (node (ref "J8") (pin "1") (pinfunction "1_1") (pintype "bidirectional"))
    )
    (net (code "102") (name "GND") (class "Default")
      (node (ref "C100") (pin "2") (pinfunction "2_2") (pintype "passive"))
      (node (ref "C20") (pin "2") (pinfunction "2_2") (pintype "passive"))
      (node (ref "C21") (pin "1") (pinfunction "1_1") (pintype "passive"))
      (node (ref "C22") (pin "2") (pinfunction "2_2") (pintype "passive"))
      (node (ref "C23") (pin "1") (pinfunction "1_1") (pintype "passive"))
      (node (ref "C24") (pin "2") (pinfunction "2_2") (pintype "passive"))
      (node (ref "C28") (pin "1") (pinfunction "1_1") (pintype "passive"))
      (node (ref "C29") (pin "1") (pinfunction "1_1") (pintype "passive"))
      (node (ref "C30") (pin "1") (pinfunction "1_1") (pintype "passive"))
      (node (ref "C31") (pin "1") (pinfunction "1_1") (pintype "passive"))
      (node (ref "C32") (pin "1") (pinfunction "1_1") (pintype "passive"))
      (node (ref "C33") (pin "1") (pinfunction "1_1") (pintype "passive"))
      (node (ref "C37") (pin "2") (pinfunction "2_2") (pintype "passive"))
      (node (ref "C98") (pin "2") (pinfunction "2_2") (pintype "passive"))
      (node (ref "C99") (pin "2") (pinfunction "2_2") (pintype "passive"))
      (node (ref "IC1") (pin "1") (pinfunction "FILTA_1") (pintype "input"))
      (node (ref "IC1") (pin "12") (pinfunction "SD1_12") (pintype "input"))
      (node (ref "IC1") (pin "13") (pinfunction "EP_13") (pintype "power_in"))
      (node (ref "IC1") (pin "5") (pinfunction "GND_5") (pintype "power_in"))
      (node (ref "IC1") (pin "6") (pinfunction "FILTB_6") (pintype "input"))
      (node (ref "IC1") (pin "7") (pinfunction "SD2_7") (pintype "input"))
      (node (ref "IC2") (pin "1") (pinfunction "FILTA_1") (pintype "input"))
      (node (ref "IC2") (pin "12") (pinfunction "SD1_12") (pintype "input"))
      (node (ref "IC2") (pin "13") (pinfunction "EP_13") (pintype "power_in"))
      (node (ref "IC2") (pin "5") (pinfunction "GND_5") (pintype "power_in"))
      (node (ref "IC2") (pin "6") (pinfunction "FILTB_6") (pintype "input"))
      (node (ref "IC2") (pin "7") (pinfunction "SD2_7") (pintype "input"))
      (node (ref "MSBOX2") (pin "1") (pinfunction "1_1") (pintype "passive"))
      (node (ref "R12") (pin "1") (pinfunction "1_1") (pintype "passive"))
      (node (ref "R38") (pin "1") (pinfunction "1_1") (pintype "passive"))
      (node (ref "R48") (pin "1") (pinfunction "1_1") (pintype "passive"))
      (node (ref "R5") (pin "1") (pinfunction "1_1") (pintype "passive"))
      (node (ref "R8") (pin "1") (pinfunction "1_1") (pintype "passive"))
      (node (ref "U1") (pin "10") (pinfunction "VEE_10") (pintype "power_in"))
      (node (ref "U1") (pin "41") (pinfunction "EP_41") (pintype "power_in"))
      (node (ref "U2") (pin "10") (pinfunction "VEE_10") (pintype "power_in"))
      (node (ref "U2") (pin "41") (pinfunction "EP_41") (pintype "power_in"))
    )
    (net (code "103") (name "Net-(C18-Pad1)") (class "Default")
      (node (ref "C18") (pin "1") (pinfunction "1_1") (pintype "passive"))
      (node (ref "C19") (pin "1") (pinfunction "1_1") (pintype "passive"))
      (node (ref "C24") (pin "1") (pinfunction "1_1") (pintype "passive"))
      (node (ref "C28") (pin "2") (pinfunction "2_2") (pintype "passive"))
      (node (ref "C29") (pin "2") (pinfunction "2_2") (pintype "passive"))
      (node (ref "C30") (pin "2") (pinfunction "2_2") (pintype "passive"))
      (node (ref "C31") (pin "2") (pinfunction "2_2") (pintype "passive"))
      (node (ref "C32") (pin "2") (pinfunction "2_2") (pintype "passive"))
      (node (ref "C33") (pin "2") (pinfunction "2_2") (pintype "passive"))
      (node (ref "L3") (pin "1") (pinfunction "1_1") (pintype "passive"))
      (node (ref "R11") (pin "1") (pinfunction "1_1") (pintype "passive"))
      (node (ref "R5") (pin "2") (pinfunction "2_2") (pintype "passive"))
      (node (ref "R8") (pin "2") (pinfunction "2_2") (pintype "passive"))
      (node (ref "U1") (pin "11") (pinfunction "VCC_11") (pintype "power_in"))
      (node (ref "U1") (pin "20") (pinfunction "VCC_20") (pintype "power_in"))
      (node (ref "U1") (pin "21") (pinfunction "VCC_21") (pintype "power_in"))
      (node (ref "U1") (pin "30") (pinfunction "VCC_30") (pintype "power_in"))
      (node (ref "U1") (pin "31") (pinfunction "VCC_31") (pintype "power_in"))
      (node (ref "U1") (pin "40") (pinfunction "VCC_40") (pintype "power_in"))
    )
    (net (code "104") (name "Net-(C34-Pad1)") (class "Default")
      (node (ref "C34") (pin "1") (pinfunction "1_1") (pintype "passive"))
      (node (ref "C35") (pin "1") (pinfunction "1_1") (pintype "passive"))
      (node (ref "C39") (pin "1") (pinfunction "1_1") (pintype "passive"))
      (node (ref "C40") (pin "2") (pinfunction "2_2") (pintype "passive"))
      (node (ref "C41") (pin "2") (pinfunction "2_2") (pintype "passive"))
      (node (ref "C42") (pin "2") (pinfunction "2_2") (pintype "passive"))
      (node (ref "C43") (pin "2") (pinfunction "2_2") (pintype "passive"))
      (node (ref "C44") (pin "2") (pinfunction "2_2") (pintype "passive"))
      (node (ref "C45") (pin "2") (pinfunction "2_2") (pintype "passive"))
      (node (ref "L11") (pin "1") (pinfunction "1_1") (pintype "passive"))
      (node (ref "R12") (pin "2") (pinfunction "2_2") (pintype "passive"))
      (node (ref "R38") (pin "2") (pinfunction "2_2") (pintype "passive"))
      (node (ref "R40") (pin "1") (pinfunction "1_1") (pintype "passive"))
      (node (ref "U2") (pin "11") (pinfunction "VCC_11") (pintype "power_in"))
      (node (ref "U2") (pin "20") (pinfunction "VCC_20") (pintype "power_in"))
      (node (ref "U2") (pin "21") (pinfunction "VCC_21") (pintype "power_in"))
      (node (ref "U2") (pin "30") (pinfunction "VCC_30") (pintype "power_in"))
      (node (ref "U2") (pin "31") (pinfunction "VCC_31") (pintype "power_in"))
      (node (ref "U2") (pin "40") (pinfunction "VCC_40") (pintype "power_in"))
    )
    (net (code "105") (name "Net-(C39-Pad2)") (class "Default")
      (node (ref "C39") (pin "2") (pinfunction "2_2") (pintype "passive"))
      (node (ref "C40") (pin "1") (pinfunction "1_1") (pintype "passive"))
      (node (ref "C41") (pin "1") (pinfunction "1_1") (pintype "passive"))
      (node (ref "C42") (pin "1") (pinfunction "1_1") (pintype "passive"))
      (node (ref "C43") (pin "1") (pinfunction "1_1") (pintype "passive"))
      (node (ref "C44") (pin "1") (pinfunction "1_1") (pintype "passive"))
      (node (ref "C45") (pin "1") (pinfunction "1_1") (pintype "passive"))
    )
    (net (code "106") (name "Net-(C100-Pad1)") (class "Default")
      (node (ref "C100") (pin "1") (pinfunction "1_1") (pintype "passive"))
      (node (ref "C37") (pin "1") (pinfunction "1_1") (pintype "passive"))
      (node (ref "C98") (pin "1") (pinfunction "1_1") (pintype "passive"))
      (node (ref "C99") (pin "1") (pinfunction "1_1") (pintype "passive"))
      (node (ref "J8") (pin "2") (pinfunction "2_2") (pintype "bidirectional"))
      (node (ref "R48") (pin "2") (pinfunction "2_2") (pintype "passive"))
    )
    (net (code "107") (name "Net-(IC1-V+)") (class "Default")
      (node (ref "C20") (pin "1") (pinfunction "1_1") (pintype "passive"))
      (node (ref "C21") (pin "2") (pinfunction "2_2") (pintype "passive"))
      (node (ref "IC1") (pin "2") (pinfunction "V+_2") (pintype "power_in"))
      (node (ref "L2") (pin "2") (pinfunction "2_2") (pintype "passive"))
    )
    (net (code "108") (name "Net-(IC2-V+)") (class "Default")
      (node (ref "C22") (pin "1") (pinfunction "1_1") (pintype "passive"))
      (node (ref "C23") (pin "2") (pinfunction "2_2") (pintype "passive"))
      (node (ref "IC2") (pin "2") (pinfunction "V+_2") (pintype "power_in"))
      (node (ref "L4") (pin "2") (pinfunction "2_2") (pintype "passive"))
    )
    (net (code "109") (name "Net-(U1-VREF0)") (class "Default")
      (node (ref "R7") (pin "2") (pinfunction "2_2") (pintype "passive"))
      (node (ref "U1") (pin "4") (pinfunction "VREF0_4") (pintype "output"))
    )
    (net (code "110") (name "Net-(U1-VREF1)") (class "Default")
      (node (ref "R9") (pin "2") (pinfunction "2_2") (pintype "passive"))
      (node (ref "U1") (pin "9") (pinfunction "VREF1_9") (pintype "output"))
    )
    (net (code "111") (name "Net-(U1-VT0)") (class "Default")
      (node (ref "C18") (pin "2") (pinfunction "2_2") (pintype "passive"))
      (node (ref "R7") (pin "1") (pinfunction "1_1") (pintype "passive"))
      (node (ref "U1") (pin "5") (pinfunction "VT0_5") (pintype "passive"))
    )
    (net (code "112") (name "Net-(U1-VT1)") (class "Default")
      (node (ref "C19") (pin "2") (pinfunction "2_2") (pintype "passive"))
      (node (ref "R9") (pin "1") (pinfunction "1_1") (pintype "passive"))
      (node (ref "U1") (pin "8") (pinfunction "VT1_8") (pintype "passive"))
    )
    (net (code "113") (name "Net-(U2-VREF0)") (class "Default")
      (node (ref "R13") (pin "2") (pinfunction "2_2") (pintype "passive"))
      (node (ref "U2") (pin "4") (pinfunction "VREF0_4") (pintype "output"))
    )
    (net (code "114") (name "Net-(U2-VREF1)") (class "Default")
      (node (ref "R39") (pin "2") (pinfunction "2_2") (pintype "passive"))
      (node (ref "U2") (pin "9") (pinfunction "VREF1_9") (pintype "output"))
    )
    (net (code "115") (name "Net-(U2-VT0)") (class "Default")
      (node (ref "C34") (pin "2") (pinfunction "2_2") (pintype "passive"))
      (node (ref "R13") (pin "1") (pinfunction "1_1") (pintype "passive"))
      (node (ref "U2") (pin "5") (pinfunction "VT0_5") (pintype "passive"))
    )
    (net (code "116") (name "Net-(U2-VT1)") (class "Default")
      (node (ref "C35") (pin "2") (pinfunction "2_2") (pintype "passive"))
      (node (ref "R39") (pin "1") (pinfunction "1_1") (pintype "passive"))
      (node (ref "U2") (pin "8") (pinfunction "VT1_8") (pintype "passive"))
    )
    (net (code "117") (name "VCCP_3V3") (class "Default")
      (node (ref "L11") (pin "2") (pinfunction "2_2") (pintype "passive"))
      (node (ref "L2") (pin "1") (pinfunction "1_1") (pintype "passive"))
      (node (ref "L3") (pin "2") (pinfunction "2_2") (pintype "passive"))
      (node (ref "L4") (pin "1") (pinfunction "1_1") (pintype "passive"))
    )
    (net (code "118") (name "unconnected-(MSBOX2-Pad2)") (class "Default")
      (node (ref "MSBOX2") (pin "2") (pinfunction "2_2") (pintype "passive+no_connect"))
    )
    (net (code "119") (name "unconnected-(MSBOX2-Pad3)") (class "Default")
      (node (ref "MSBOX2") (pin "3") (pinfunction "3_3") (pintype "passive+no_connect"))
    )
    (net (code "120") (name "unconnected-(MSBOX2-Pad4)") (class "Default")
      (node (ref "MSBOX2") (pin "4") (pinfunction "4_4") (pintype "passive+no_connect"))
    )
    (net (code "121") (name "unconnected-(MSBOX2-Pad5)") (class "Default")
      (node (ref "MSBOX2") (pin "5") (pinfunction "5_5") (pintype "passive+no_connect"))
    )
    (net (code "122") (name "unconnected-(U1-Q11-Pad13)") (class "Default")
      (node (ref "U1") (pin "13") (pinfunction "Q11_13") (pintype "open_emitter+no_connect"))
    )
    (net (code "123") (name "unconnected-(U1-~{Q11}-Pad12)") (class "Default")
      (node (ref "U1") (pin "12") (pinfunction "~{Q11}_12") (pintype "open_emitter+no_connect"))
    )
  )
)
